# Core.net
KiCad netlist of a schematic drawn in Altium Designer
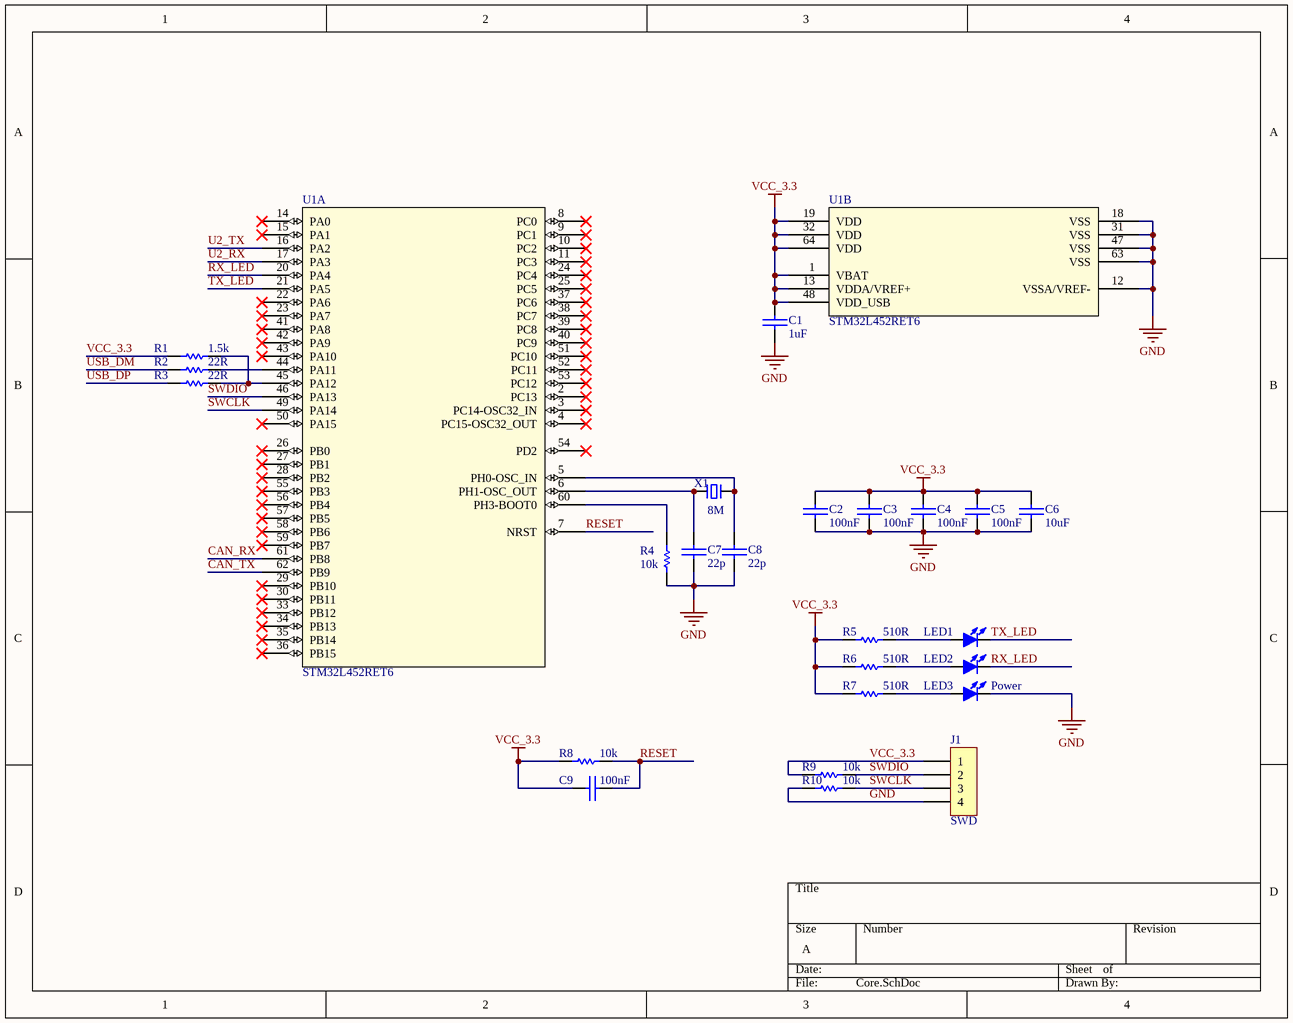
[diagram p0: Core.SchDoc]

(export (version "E")
  (design (tool "Eeschema 10.0.6"))
  (components
    (comp (ref "C1")
      (value "1uF")
      (footprint "C 0603_L")
      (description "无极性电容")
      (libsource (lib "电容") (part "CAP"))
    )
    (comp (ref "C2")
      (value "100nF")
      (footprint "C 0603_L")
      (description "无极性电容")
      (libsource (lib "电容") (part "CAP"))
    )
    (comp (ref "C3")
      (value "100nF")
      (footprint "C 0603_L")
      (description "无极性电容")
      (libsource (lib "电容") (part "CAP"))
    )
    (comp (ref "C4")
      (value "100nF")
      (footprint "C 0603_L")
      (description "无极性电容")
      (libsource (lib "电容") (part "CAP"))
    )
    (comp (ref "C5")
      (value "100nF")
      (footprint "C 0603_L")
      (description "无极性电容")
      (libsource (lib "电容") (part "CAP"))
    )
    (comp (ref "C6")
      (value "10uF")
      (footprint "C 0603_L")
      (description "无极性电容")
      (libsource (lib "电容") (part "CAP"))
    )
    (comp (ref "C7")
      (value "22p")
      (footprint "C 0603_L")
      (description "无极性电容")
      (libsource (lib "电容") (part "CAP"))
    )
    (comp (ref "C8")
      (value "22p")
      (footprint "C 0603_L")
      (description "无极性电容")
      (libsource (lib "电容") (part "CAP"))
    )
    (comp (ref "C9")
      (value "100nF")
      (footprint "C 0603_L")
      (description "无极性电容")
      (libsource (lib "电容") (part "CAP"))
    )
    (comp (ref "J1")
      (value "SWD")
      (footprint "Pin HDR1X4/2.54mm-S")
      (libsource (lib "排针") (part "Pin HDR1X4"))
    )
    (comp (ref "LED1")
      (value "CAN_TX")
      (footprint "LED 0805R")
      (description "贴片LED")
      (fields (field (name "版权归属") "封装库来自淘宝 ID：黄晶宝石"))
      (libsource (lib "0.3 - LED发光二极管") (part "LED-SMD"))
    )
    (comp (ref "LED2")
      (value "CAN_RX")
      (footprint "LED 0805G")
      (description "贴片LED")
      (fields (field (name "版权归属") "封装库来自淘宝 ID：黄晶宝石"))
      (libsource (lib "0.3 - LED发光二极管") (part "LED-SMD"))
    )
    (comp (ref "LED3")
      (value "Power")
      (footprint "LED 0805B")
      (description "贴片LED")
      (fields (field (name "版权归属") "封装库来自淘宝 ID：黄晶宝石"))
      (libsource (lib "0.3 - LED发光二极管") (part "LED-SMD"))
    )
    (comp (ref "R1") (value "1.5k") (footprint "0603R") (libsource (lib "电阻") (part "RES")))
    (comp (ref "R2") (value "22R") (footprint "0603R") (libsource (lib "电阻") (part "RES")))
    (comp (ref "R3") (value "22R") (footprint "0603R") (libsource (lib "电阻") (part "RES")))
    (comp (ref "R4") (value "10k") (footprint "0603R") (libsource (lib "电阻") (part "RES")))
    (comp (ref "R5") (value "510R") (footprint "0603R") (libsource (lib "电阻") (part "RES")))
    (comp (ref "R6") (value "510R") (footprint "0603R") (libsource (lib "电阻") (part "RES")))
    (comp (ref "R7") (value "510R") (footprint "0603R") (libsource (lib "电阻") (part "RES")))
    (comp (ref "R8") (value "10k") (footprint "0603R") (libsource (lib "电阻") (part "RES")))
    (comp (ref "R9") (value "10k") (footprint "0603R") (libsource (lib "电阻") (part "RES")))
    (comp (ref "R10") (value "10k") (footprint "0603R") (libsource (lib "电阻") (part "RES")))
    (comp (ref "U1")
      (value "STM32L452RET6")
      (footprint "LQFP64-10*10")
      (description "No Description Available")
      (libsource (lib "STM32L452RET6") (part "STM32L452RET6"))
    )
    (comp (ref "X1")
      (value "8M")
      (footprint "OSC HC-49S")
      (description "2脚无源脚晶振")
      (libsource (lib "晶振") (part "XTAL-2P"))
    )
  )
  (nets
    (net (code "1") (name "/CAN_RX") (class "Default")
      (node (ref "U1") (pin "61") (pinfunction "PB8_61") (pintype "bidirectional"))
    )
    (net (code "2") (name "/CAN_TX") (class "Default")
      (node (ref "U1") (pin "62") (pinfunction "PB9_62") (pintype "bidirectional"))
    )
    (net (code "3") (name "/RESET") (class "Default")
      (node (ref "C9") (pin "1") (pinfunction "1_1") (pintype "passive"))
      (node (ref "R8") (pin "2") (pinfunction "2_2") (pintype "passive"))
      (node (ref "U1") (pin "7") (pinfunction "NRST_7") (pintype "bidirectional"))
    )
    (net (code "4") (name "/RX_LED") (class "Default")
      (node (ref "LED2") (pin "2") (pinfunction "K_2") (pintype "passive"))
      (node (ref "U1") (pin "20") (pinfunction "PA4_20") (pintype "bidirectional"))
    )
    (net (code "5") (name "/SWCLK") (class "Default")
      (node (ref "J1") (pin "3") (pinfunction "3_3") (pintype "passive"))
      (node (ref "R10") (pin "2") (pinfunction "2_2") (pintype "passive"))
      (node (ref "U1") (pin "49") (pinfunction "PA14_49") (pintype "bidirectional"))
    )
    (net (code "6") (name "/SWDIO") (class "Default")
      (node (ref "J1") (pin "2") (pinfunction "2_2") (pintype "passive"))
      (node (ref "R9") (pin "2") (pinfunction "2_2") (pintype "passive"))
      (node (ref "U1") (pin "46") (pinfunction "PA13_46") (pintype "bidirectional"))
    )
    (net (code "7") (name "/TX_LED") (class "Default")
      (node (ref "LED1") (pin "2") (pinfunction "K_2") (pintype "passive"))
      (node (ref "U1") (pin "21") (pinfunction "PA5_21") (pintype "bidirectional"))
    )
    (net (code "8") (name "/U2_RX") (class "Default")
      (node (ref "U1") (pin "17") (pinfunction "PA3_17") (pintype "bidirectional"))
    )
    (net (code "9") (name "/U2_TX") (class "Default")
      (node (ref "U1") (pin "16") (pinfunction "PA2_16") (pintype "bidirectional"))
    )
    (net (code "10") (name "/USB_DM") (class "Default")
      (node (ref "R2") (pin "1") (pinfunction "1_1") (pintype "passive"))
    )
    (net (code "11") (name "/USB_DP") (class "Default")
      (node (ref "R3") (pin "1") (pinfunction "1_1") (pintype "passive"))
    )
    (net (code "12") (name "GND") (class "Default")
      (node (ref "C1") (pin "1") (pinfunction "1_1") (pintype "passive"))
      (node (ref "C2") (pin "1") (pinfunction "1_1") (pintype "passive"))
      (node (ref "C3") (pin "1") (pinfunction "1_1") (pintype "passive"))
      (node (ref "C4") (pin "1") (pinfunction "1_1") (pintype "passive"))
      (node (ref "C5") (pin "1") (pinfunction "1_1") (pintype "passive"))
      (node (ref "C6") (pin "1") (pinfunction "1_1") (pintype "passive"))
      (node (ref "C7") (pin "1") (pinfunction "1_1") (pintype "passive"))
      (node (ref "C8") (pin "1") (pinfunction "1_1") (pintype "passive"))
      (node (ref "J1") (pin "4") (pinfunction "4_4") (pintype "passive"))
      (node (ref "LED3") (pin "2") (pinfunction "K_2") (pintype "passive"))
      (node (ref "R10") (pin "1") (pinfunction "1_1") (pintype "passive"))
      (node (ref "R4") (pin "1") (pinfunction "1_1") (pintype "passive"))
      (node (ref "U1") (pin "12") (pinfunction "VSSA/VREF-_12") (pintype "power_in"))
      (node (ref "U1") (pin "18") (pinfunction "VSS_18") (pintype "power_in"))
      (node (ref "U1") (pin "31") (pinfunction "VSS_31") (pintype "power_in"))
      (node (ref "U1") (pin "47") (pinfunction "VSS_47") (pintype "power_in"))
      (node (ref "U1") (pin "63") (pinfunction "VSS_63") (pintype "power_in"))
    )
    (net (code "13") (name "Net-(LED1-A)") (class "Default")
      (node (ref "LED1") (pin "1") (pinfunction "A_1") (pintype "passive"))
      (node (ref "R5") (pin "2") (pinfunction "2_2") (pintype "passive"))
    )
    (net (code "14") (name "Net-(LED2-A)") (class "Default")
      (node (ref "LED2") (pin "1") (pinfunction "A_1") (pintype "passive"))
      (node (ref "R6") (pin "2") (pinfunction "2_2") (pintype "passive"))
    )
    (net (code "15") (name "Net-(LED3-A)") (class "Default")
      (node (ref "LED3") (pin "1") (pinfunction "A_1") (pintype "passive"))
      (node (ref "R7") (pin "2") (pinfunction "2_2") (pintype "passive"))
    )
    (net (code "16") (name "Net-(U1A-PA11)") (class "Default")
      (node (ref "R2") (pin "2") (pinfunction "2_2") (pintype "passive"))
      (node (ref "U1") (pin "44") (pinfunction "PA11_44") (pintype "bidirectional"))
    )
    (net (code "17") (name "Net-(U1A-PA12)") (class "Default")
      (node (ref "R1") (pin "2") (pinfunction "2_2") (pintype "passive"))
      (node (ref "R3") (pin "2") (pinfunction "2_2") (pintype "passive"))
      (node (ref "U1") (pin "45") (pinfunction "PA12_45") (pintype "bidirectional"))
    )
    (net (code "18") (name "Net-(U1A-PH0-OSC_IN)") (class "Default")
      (node (ref "C8") (pin "2") (pinfunction "2_2") (pintype "passive"))
      (node (ref "U1") (pin "5") (pinfunction "PH0-OSC_IN_5") (pintype "bidirectional"))
      (node (ref "X1") (pin "2") (pinfunction "2_2") (pintype "passive"))
    )
    (net (code "19") (name "Net-(U1A-PH1-OSC_OUT)") (class "Default")
      (node (ref "C7") (pin "2") (pinfunction "2_2") (pintype "passive"))
      (node (ref "U1") (pin "6") (pinfunction "PH1-OSC_OUT_6") (pintype "bidirectional"))
      (node (ref "X1") (pin "1") (pinfunction "1_1") (pintype "passive"))
    )
    (net (code "20") (name "Net-(U1A-PH3-BOOT0)") (class "Default")
      (node (ref "R4") (pin "2") (pinfunction "2_2") (pintype "passive"))
      (node (ref "U1") (pin "60") (pinfunction "PH3-BOOT0_60") (pintype "bidirectional"))
    )
    (net (code "21") (name "VCC_3.3") (class "Default")
      (node (ref "C1") (pin "2") (pinfunction "2_2") (pintype "passive"))
      (node (ref "C2") (pin "2") (pinfunction "2_2") (pintype "passive"))
      (node (ref "C3") (pin "2") (pinfunction "2_2") (pintype "passive"))
      (node (ref "C4") (pin "2") (pinfunction "2_2") (pintype "passive"))
      (node (ref "C5") (pin "2") (pinfunction "2_2") (pintype "passive"))
      (node (ref "C6") (pin "2") (pinfunction "2_2") (pintype "passive"))
      (node (ref "C9") (pin "2") (pinfunction "2_2") (pintype "passive"))
      (node (ref "J1") (pin "1") (pinfunction "1_1") (pintype "passive"))
      (node (ref "R1") (pin "1") (pinfunction "1_1") (pintype "passive"))
      (node (ref "R5") (pin "1") (pinfunction "1_1") (pintype "passive"))
      (node (ref "R6") (pin "1") (pinfunction "1_1") (pintype "passive"))
      (node (ref "R7") (pin "1") (pinfunction "1_1") (pintype "passive"))
      (node (ref "R8") (pin "1") (pinfunction "1_1") (pintype "passive"))
      (node (ref "R9") (pin "1") (pinfunction "1_1") (pintype "passive"))
      (node (ref "U1") (pin "1") (pinfunction "VBAT_1") (pintype "power_in"))
      (node (ref "U1") (pin "13") (pinfunction "VDDA/VREF+_13") (pintype "power_in"))
      (node (ref "U1") (pin "19") (pinfunction "VDD_19") (pintype "power_in"))
      (node (ref "U1") (pin "32") (pinfunction "VDD_32") (pintype "power_in"))
      (node (ref "U1") (pin "48") (pinfunction "VDD_USB_48") (pintype "power_in"))
      (node (ref "U1") (pin "64") (pinfunction "VDD_64") (pintype "power_in"))
    )
    (net (code "22") (name "unconnected-(U1A-PA0-Pad14)") (class "Default")
      (node (ref "U1") (pin "14") (pinfunction "PA0_14") (pintype "bidirectional+no_connect"))
    )
    (net (code "23") (name "unconnected-(U1A-PA1-Pad15)") (class "Default")
      (node (ref "U1") (pin "15") (pinfunction "PA1_15") (pintype "bidirectional+no_connect"))
    )
    (net (code "24") (name "unconnected-(U1A-PA6-Pad22)") (class "Default")
      (node (ref "U1") (pin "22") (pinfunction "PA6_22") (pintype "bidirectional+no_connect"))
    )
    (net (code "25") (name "unconnected-(U1A-PA7-Pad23)") (class "Default")
      (node (ref "U1") (pin "23") (pinfunction "PA7_23") (pintype "bidirectional+no_connect"))
    )
    (net (code "26") (name "unconnected-(U1A-PA8-Pad41)") (class "Default")
      (node (ref "U1") (pin "41") (pinfunction "PA8_41") (pintype "bidirectional+no_connect"))
    )
    (net (code "27") (name "unconnected-(U1A-PA9-Pad42)") (class "Default")
      (node (ref "U1") (pin "42") (pinfunction "PA9_42") (pintype "bidirectional+no_connect"))
    )
    (net (code "28") (name "unconnected-(U1A-PA10-Pad43)") (class "Default")
      (node (ref "U1") (pin "43") (pinfunction "PA10_43") (pintype "bidirectional+no_connect"))
    )
    (net (code "29") (name "unconnected-(U1A-PA15-Pad50)") (class "Default")
      (node (ref "U1") (pin "50") (pinfunction "PA15_50") (pintype "bidirectional+no_connect"))
    )
    (net (code "30") (name "unconnected-(U1A-PB0-Pad26)") (class "Default")
      (node (ref "U1") (pin "26") (pinfunction "PB0_26") (pintype "bidirectional+no_connect"))
    )
    (net (code "31") (name "unconnected-(U1A-PB1-Pad27)") (class "Default")
      (node (ref "U1") (pin "27") (pinfunction "PB1_27") (pintype "bidirectional+no_connect"))
    )
    (net (code "32") (name "unconnected-(U1A-PB2-Pad28)") (class "Default")
      (node (ref "U1") (pin "28") (pinfunction "PB2_28") (pintype "bidirectional+no_connect"))
    )
    (net (code "33") (name "unconnected-(U1A-PB3-Pad55)") (class "Default")
      (node (ref "U1") (pin "55") (pinfunction "PB3_55") (pintype "bidirectional+no_connect"))
    )
    (net (code "34") (name "unconnected-(U1A-PB4-Pad56)") (class "Default")
      (node (ref "U1") (pin "56") (pinfunction "PB4_56") (pintype "bidirectional+no_connect"))
    )
    (net (code "35") (name "unconnected-(U1A-PB5-Pad57)") (class "Default")
      (node (ref "U1") (pin "57") (pinfunction "PB5_57") (pintype "bidirectional+no_connect"))
    )
    (net (code "36") (name "unconnected-(U1A-PB6-Pad58)") (class "Default")
      (node (ref "U1") (pin "58") (pinfunction "PB6_58") (pintype "bidirectional+no_connect"))
    )
    (net (code "37") (name "unconnected-(U1A-PB7-Pad59)") (class "Default")
      (node (ref "U1") (pin "59") (pinfunction "PB7_59") (pintype "bidirectional+no_connect"))
    )
    (net (code "38") (name "unconnected-(U1A-PB10-Pad29)") (class "Default")
      (node (ref "U1") (pin "29") (pinfunction "PB10_29") (pintype "bidirectional+no_connect"))
    )
    (net (code "39") (name "unconnected-(U1A-PB11-Pad30)") (class "Default")
      (node (ref "U1") (pin "30") (pinfunction "PB11_30") (pintype "bidirectional+no_connect"))
    )
    (net (code "40") (name "unconnected-(U1A-PB12-Pad33)") (class "Default")
      (node (ref "U1") (pin "33") (pinfunction "PB12_33") (pintype "bidirectional+no_connect"))
    )
    (net (code "41") (name "unconnected-(U1A-PB13-Pad34)") (class "Default")
      (node (ref "U1") (pin "34") (pinfunction "PB13_34") (pintype "bidirectional+no_connect"))
    )
    (net (code "42") (name "unconnected-(U1A-PB14-Pad35)") (class "Default")
      (node (ref "U1") (pin "35") (pinfunction "PB14_35") (pintype "bidirectional+no_connect"))
    )
    (net (code "43") (name "unconnected-(U1A-PB15-Pad36)") (class "Default")
      (node (ref "U1") (pin "36") (pinfunction "PB15_36") (pintype "bidirectional+no_connect"))
    )
    (net (code "44") (name "unconnected-(U1A-PC0-Pad8)") (class "Default")
      (node (ref "U1") (pin "8") (pinfunction "PC0_8") (pintype "bidirectional+no_connect"))
    )
    (net (code "45") (name "unconnected-(U1A-PC1-Pad9)") (class "Default")
      (node (ref "U1") (pin "9") (pinfunction "PC1_9") (pintype "bidirectional+no_connect"))
    )
    (net (code "46") (name "unconnected-(U1A-PC2-Pad10)") (class "Default")
      (node (ref "U1") (pin "10") (pinfunction "PC2_10") (pintype "bidirectional+no_connect"))
    )
    (net (code "47") (name "unconnected-(U1A-PC3-Pad11)") (class "Default")
      (node (ref "U1") (pin "11") (pinfunction "PC3_11") (pintype "bidirectional+no_connect"))
    )
    (net (code "48") (name "unconnected-(U1A-PC4-Pad24)") (class "Default")
      (node (ref "U1") (pin "24") (pinfunction "PC4_24") (pintype "bidirectional+no_connect"))
    )
    (net (code "49") (name "unconnected-(U1A-PC5-Pad25)") (class "Default")
      (node (ref "U1") (pin "25") (pinfunction "PC5_25") (pintype "bidirectional+no_connect"))
    )
    (net (code "50") (name "unconnected-(U1A-PC6-Pad37)") (class "Default")
      (node (ref "U1") (pin "37") (pinfunction "PC6_37") (pintype "bidirectional+no_connect"))
    )
    (net (code "51") (name "unconnected-(U1A-PC7-Pad38)") (class "Default")
      (node (ref "U1") (pin "38") (pinfunction "PC7_38") (pintype "bidirectional+no_connect"))
    )
    (net (code "52") (name "unconnected-(U1A-PC8-Pad39)") (class "Default")
      (node (ref "U1") (pin "39") (pinfunction "PC8_39") (pintype "bidirectional+no_connect"))
    )
    (net (code "53") (name "unconnected-(U1A-PC9-Pad40)") (class "Default")
      (node (ref "U1") (pin "40") (pinfunction "PC9_40") (pintype "bidirectional+no_connect"))
    )
    (net (code "54") (name "unconnected-(U1A-PC10-Pad51)") (class "Default")
      (node (ref "U1") (pin "51") (pinfunction "PC10_51") (pintype "bidirectional+no_connect"))
    )
    (net (code "55") (name "unconnected-(U1A-PC11-Pad52)") (class "Default")
      (node (ref "U1") (pin "52") (pinfunction "PC11_52") (pintype "bidirectional+no_connect"))
    )
    (net (code "56") (name "unconnected-(U1A-PC12-Pad53)") (class "Default")
      (node (ref "U1") (pin "53") (pinfunction "PC12_53") (pintype "bidirectional+no_connect"))
    )
    (net (code "57") (name "unconnected-(U1A-PC13-Pad2)") (class "Default")
      (node (ref "U1") (pin "2") (pinfunction "PC13_2") (pintype "bidirectional+no_connect"))
    )
    (net (code "58") (name "unconnected-(U1A-PC14-OSC32_IN-Pad3)") (class "Default")
      (node (ref "U1") (pin "3") (pinfunction "PC14-OSC32_IN_3") (pintype "bidirectional+no_connect"))
    )
    (net (code "59") (name "unconnected-(U1A-PC15-OSC32_OUT-Pad4)") (class "Default")
      (node (ref "U1") (pin "4") (pinfunction "PC15-OSC32_OUT_4") (pintype "bidirectional+no_connect"))
    )
    (net (code "60") (name "unconnected-(U1A-PD2-Pad54)") (class "Default")
      (node (ref "U1") (pin "54") (pinfunction "PD2_54") (pintype "bidirectional+no_connect"))
    )
  )
)
